# IO_Peripherals.net
KiCad netlist of a schematic drawn in Altium Designer
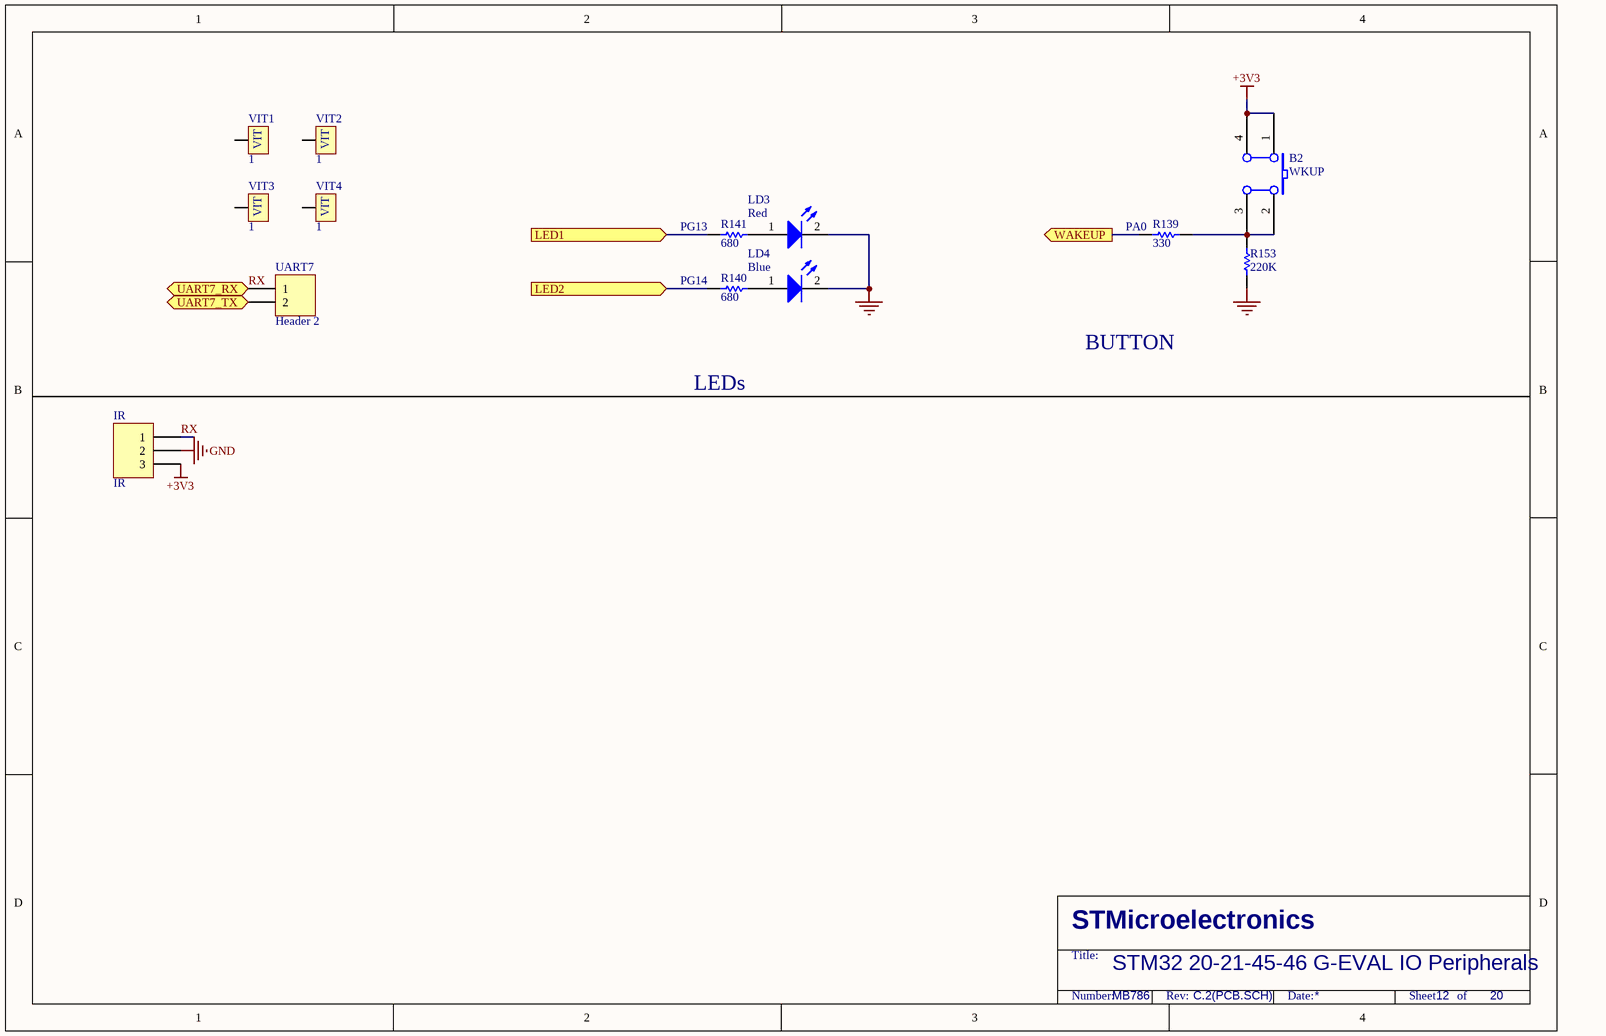
[diagram p0: IO Peripherals.SchDoc]

(export (version "E")
  (design (tool "Eeschema 10.0.6"))
  (components
    (comp (ref "B2")
      (value "WKUP")
      (footprint "PB")
      (description "SE PUSHBUTTON")
      (libsource (lib "Documents") (part "SW PUSHBUTTON"))
    )
    (comp (ref "IR")
      (value "IR")
      (footprint "HDR1X3")
      (description "Header, 3-Pin")
      (fields (field (name "PUBLISHER") "Altium Limited"))
      (libsource (lib "Miscellaneous Connectors") (part "Header 3"))
    )
    (comp (ref "LD3")
      (value "Red")
      (footprint "0805_LED")
      (description "Typical RED, GREEN, YELLOW, AMBER GaAs LED")
      (fields (field (name "PUBLISHER") "Altium Limited"))
      (libsource (lib "Miscellaneous Devices") (part "LED2"))
    )
    (comp (ref "LD4")
      (value "Blue")
      (footprint "0805_LED")
      (description "Typical RED, GREEN, YELLOW, AMBER GaAs LED")
      (fields (field (name "PUBLISHER") "Altium Limited"))
      (libsource (lib "Miscellaneous Devices") (part "LED2"))
    )
    (comp (ref "R139")
      (value "330")
      (footprint "0603_R")
      (description "Resistor")
      (fields (field (name "PUBLISHER") "Altium Limited"))
      (libsource (lib "Miscellaneous Devices") (part "Res1"))
    )
    (comp (ref "R140")
      (value "680")
      (footprint "0603_R")
      (description "Resistor")
      (fields (field (name "PUBLISHER") "Altium Limited"))
      (libsource (lib "Miscellaneous Devices") (part "Res1"))
    )
    (comp (ref "R141")
      (value "680")
      (footprint "0603_R")
      (description "Resistor")
      (fields (field (name "PUBLISHER") "Altium Limited"))
      (libsource (lib "Miscellaneous Devices") (part "Res1"))
    )
    (comp (ref "R153")
      (value "220K")
      (footprint "0603_R")
      (description "Resistor")
      (fields (field (name "PUBLISHER") "Altium Limited"))
      (libsource (lib "Miscellaneous Devices") (part "res1"))
    )
    (comp (ref "UART7")
      (value "Header 2")
      (footprint "HDR1X2")
      (description "Header, 2-Pin")
      (fields (field (name "PUBLISHER") "Altium Limited"))
      (libsource (lib "Miscellaneous Connectors") (part "Header 2"))
    )
    (comp (ref "VIT1")
      (value "1")
      (footprint "VIT")
      (description "Oc Vit")
      (libsource (lib "Cty1") (part "VIT"))
    )
    (comp (ref "VIT2")
      (value "1")
      (footprint "VIT")
      (description "Oc Vit")
      (libsource (lib "Cty1") (part "VIT"))
    )
    (comp (ref "VIT3")
      (value "1")
      (footprint "VIT")
      (description "Oc Vit")
      (libsource (lib "Cty1") (part "VIT"))
    )
    (comp (ref "VIT4")
      (value "1")
      (footprint "VIT")
      (description "Oc Vit")
      (libsource (lib "Cty1") (part "VIT"))
    )
  )
  (nets
    (net (code "1") (name "+3V3") (class "Default")
      (node (ref "B2") (pin "1") (pinfunction "A0_1") (pintype "passive"))
      (node (ref "B2") (pin "4") (pinfunction "A1_4") (pintype "passive"))
      (node (ref "IR") (pin "3") (pinfunction "3_3") (pintype "passive"))
    )
    (net (code "2") (name "/LED1") (class "Default")
      (node (ref "R141") (pin "2") (pinfunction "2_2") (pintype "passive"))
    )
    (net (code "3") (name "/LED2") (class "Default")
      (node (ref "R140") (pin "2") (pinfunction "2_2") (pintype "passive"))
    )
    (net (code "4") (name "/RX") (class "Default")
      (node (ref "IR") (pin "1") (pinfunction "1_1") (pintype "passive"))
      (node (ref "UART7") (pin "1") (pinfunction "1_1") (pintype "passive"))
    )
    (net (code "5") (name "/UART7_TX") (class "Default")
      (node (ref "UART7") (pin "2") (pinfunction "2_2") (pintype "passive"))
    )
    (net (code "6") (name "/WAKEUP") (class "Default")
      (node (ref "R139") (pin "2") (pinfunction "2_2") (pintype "passive"))
    )
    (net (code "7") (name "GND") (class "Default")
      (node (ref "IR") (pin "2") (pinfunction "2_2") (pintype "passive"))
      (node (ref "LD3") (pin "2") (pinfunction "K_2") (pintype "passive"))
      (node (ref "LD4") (pin "2") (pinfunction "K_2") (pintype "passive"))
      (node (ref "R153") (pin "2") (pinfunction "2_2") (pintype "passive"))
    )
    (net (code "8") (name "Net-(B2-B0)") (class "Default")
      (node (ref "B2") (pin "2") (pinfunction "B0_2") (pintype "passive"))
      (node (ref "B2") (pin "3") (pinfunction "B1_3") (pintype "passive"))
      (node (ref "R139") (pin "1") (pinfunction "1_1") (pintype "passive"))
      (node (ref "R153") (pin "1") (pinfunction "1_1") (pintype "passive"))
    )
    (net (code "9") (name "Net-(LD3-A)") (class "Default")
      (node (ref "LD3") (pin "1") (pinfunction "A_1") (pintype "passive"))
      (node (ref "R141") (pin "1") (pinfunction "1_1") (pintype "passive"))
    )
    (net (code "10") (name "Net-(LD4-A)") (class "Default")
      (node (ref "LD4") (pin "1") (pinfunction "A_1") (pintype "passive"))
      (node (ref "R140") (pin "1") (pinfunction "1_1") (pintype "passive"))
    )
    (net (code "11") (name "unconnected-(VIT1-1-PadVIT1)") (class "Default")
      (node (ref "VIT1") (pin "VIT1") (pinfunction "1_VIT1") (pintype "passive"))
    )
    (net (code "12") (name "unconnected-(VIT2-1-PadVIT1)") (class "Default")
      (node (ref "VIT2") (pin "VIT1") (pinfunction "1_VIT1") (pintype "passive"))
    )
    (net (code "13") (name "unconnected-(VIT3-1-PadVIT1)") (class "Default")
      (node (ref "VIT3") (pin "VIT1") (pinfunction "1_VIT1") (pintype "passive"))
    )
    (net (code "14") (name "unconnected-(VIT4-1-PadVIT1)") (class "Default")
      (node (ref "VIT4") (pin "VIT1") (pinfunction "1_VIT1") (pintype "passive"))
    )
  )
)
